# Car_Circuitry.net
KiCad netlist of a schematic drawn in Altium Designer
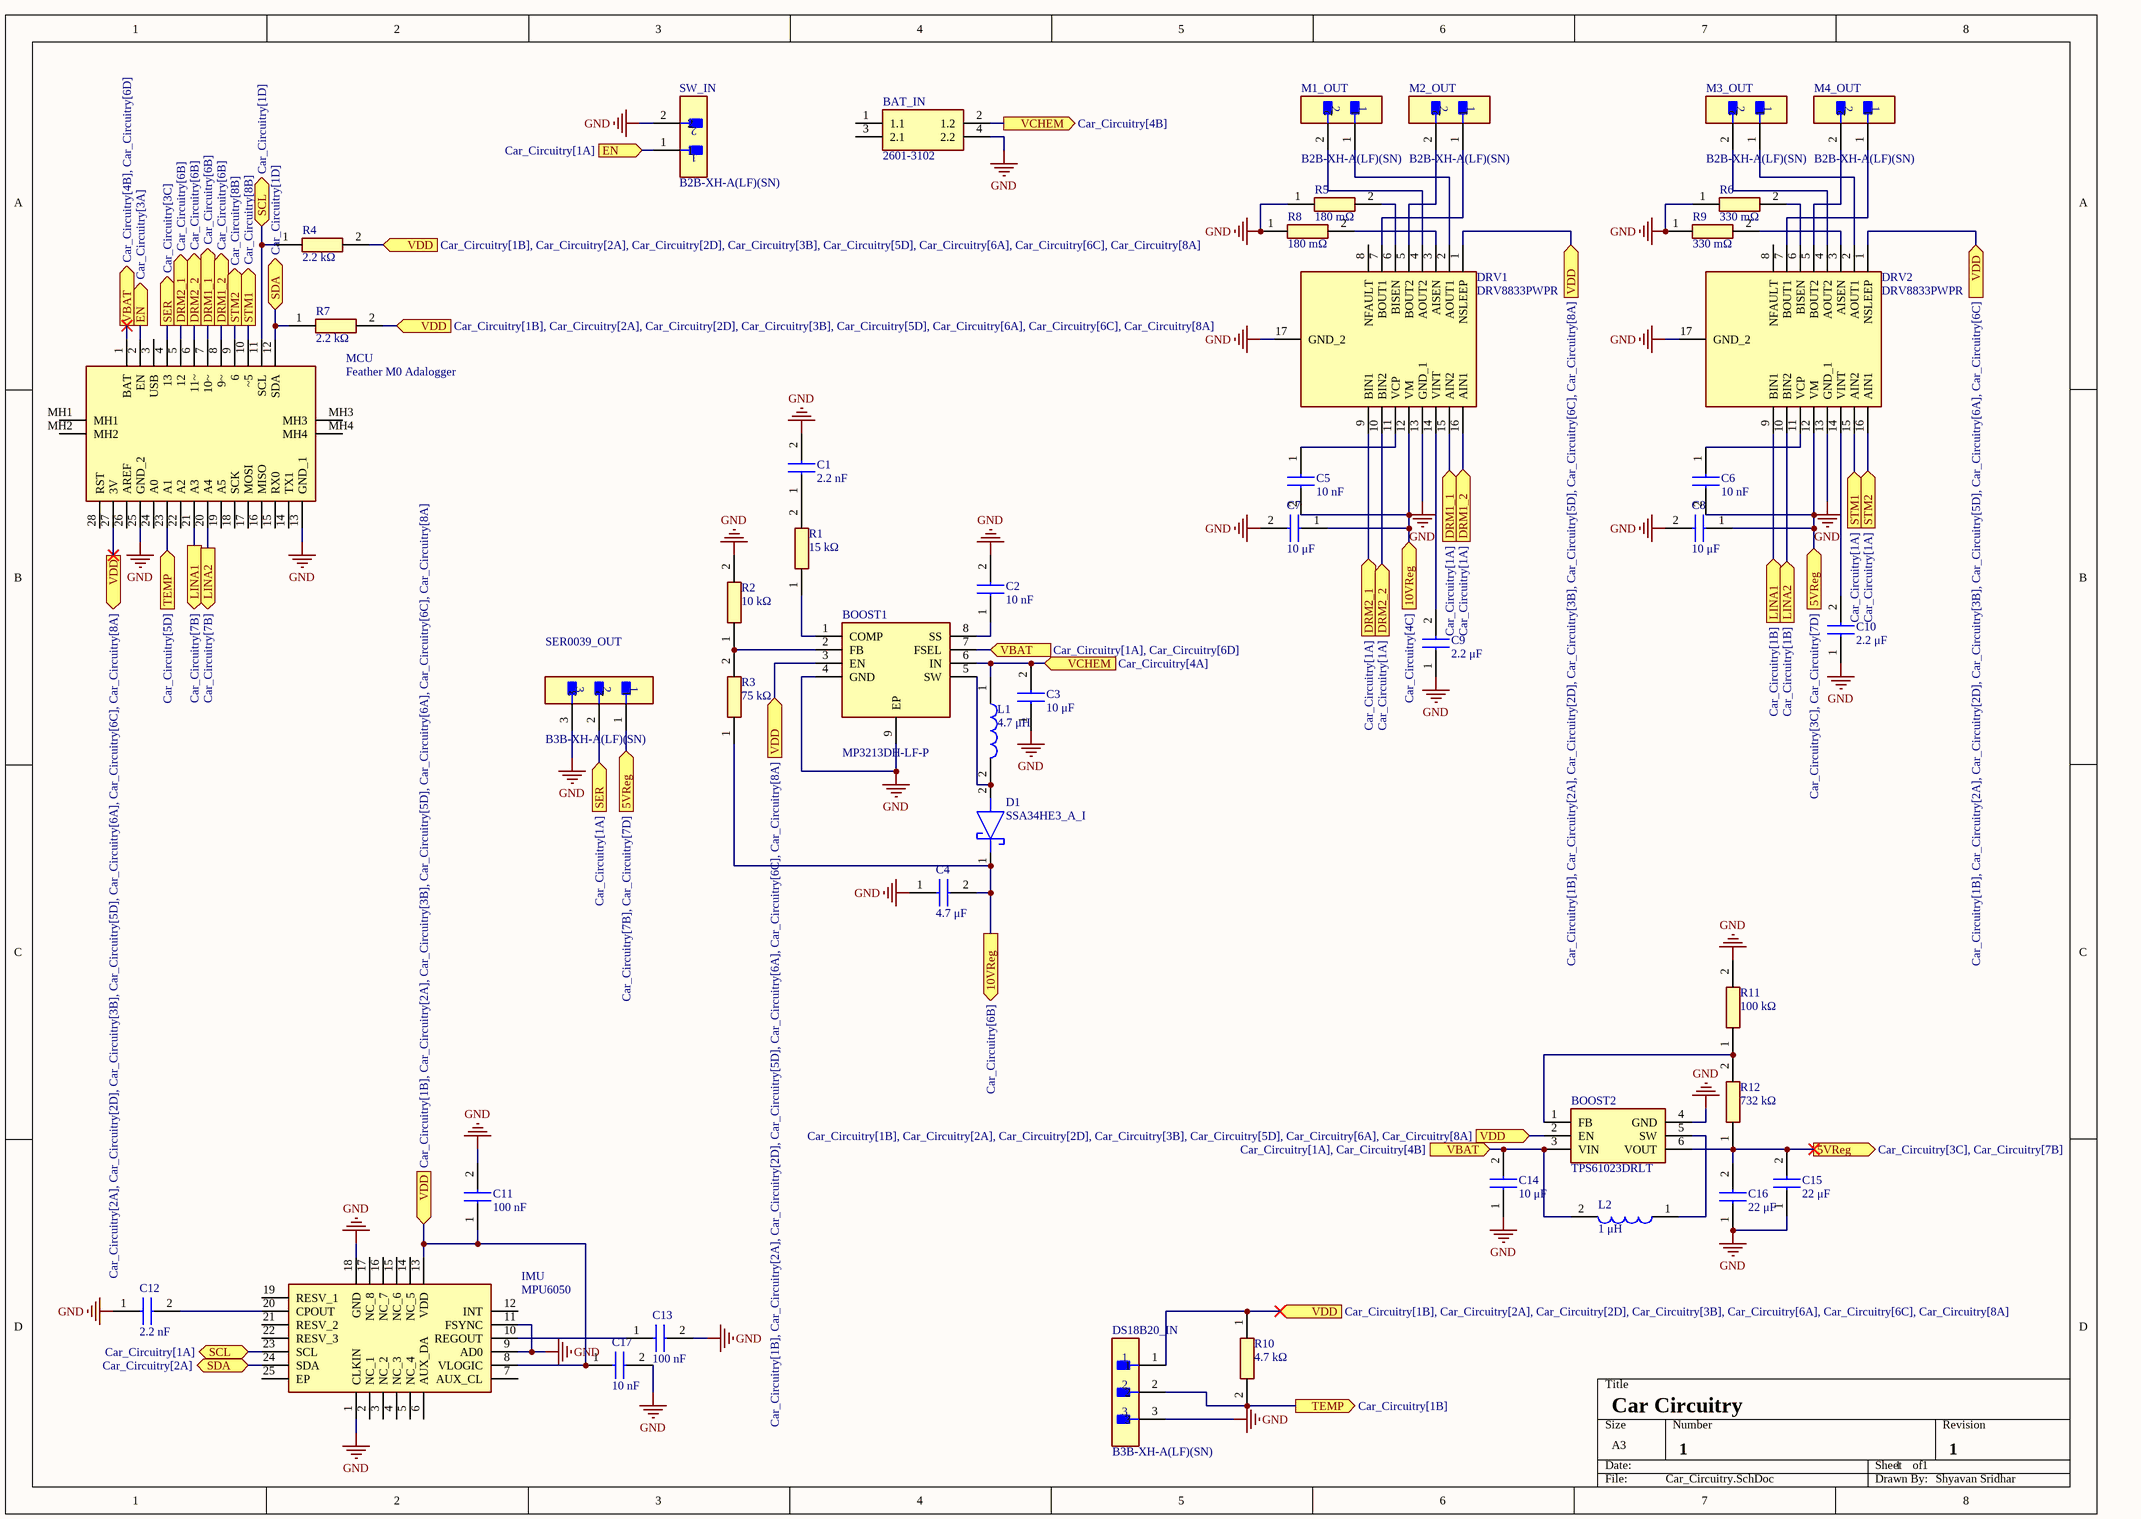
[diagram p0: Car_Circuitry.SchDoc]

(export (version "E")
  (design (tool "Eeschema 10.0.6"))
  (components
    (comp (ref "BAT_IN")
      (value "2601-3102")
      (footprint "SamacSys:26013102")
      (description "WAGO Terminal Block")
      (libsource (lib "*") (part "2601-3102"))
    )
    (comp (ref "BOOST1")
      (value "MP3213DH-LF-P")
      (footprint "SamacSys:SOP65P490X110-9N")
      (description "Integrated Circuit")
      (fields (field (name "MOUSER PART NUMBER") "946-MP3213DHLFP"))
      (libsource (lib "*") (part "MP3213DH-LF-P"))
    )
    (comp (ref "BOOST2")
      (value "TPS61023DRLT")
      (footprint "SamacSys:SOTFL50P160X60-6N")
      (description "Integrated Circuit")
      (fields (field (name "MOUSER PART NUMBER") "595-TPS61023DRLT"))
      (libsource (lib "*") (part "TPS61023DRLT"))
    )
    (comp (ref "C1")
      (value "2.2 nF")
      (footprint "SamacSys:CAPC2012X75N")
      (description "Capacitor")
      (fields (field (name "MANUFACTURER_PART_NUMBER") "CL21B222KBANNNC"))
      (libsource (lib "*") (part "CL21B222KBANNNC"))
    )
    (comp (ref "C2")
      (value "10 nF")
      (footprint "SamacSys:CAPC2012X75N")
      (description "Capacitor")
      (fields
        (field (name "MANUFACTURER_PART_NUMBER") "CL21B103KBANNNC")
        (field (name "MOUSER PART NUMBER") "187-CL21B103KBANNNC")
      )
      (libsource (lib "*") (part "CL21B103KBANNNC"))
    )
    (comp (ref "C3")
      (value "10 μF")
      (footprint "SamacSys:CAPC2012X140N")
      (description "Capacitor")
      (fields
        (field (name "MANUFACTURER_PART_NUMBER") "CL21B106KOQNNNE")
        (field (name "MOUSER PART NUMBER") "187-CL21B106KOQNNNE")
      )
      (libsource (lib "*") (part "CL21B106KOQNNNE"))
    )
    (comp (ref "C4")
      (value "4.7 μF")
      (footprint "SamacSys:CAPC2012X135N")
      (description "Capacitor")
      (fields
        (field (name "MANUFACTURER_PART_NUMBER") "CL21B475KOFNNNE")
        (field (name "MOUSER PART NUMBER") "187-CL21B475KOFNNNE")
      )
      (libsource (lib "*") (part "CL21B475KOFNNNE"))
    )
    (comp (ref "C5")
      (value "10 nF")
      (footprint "SamacSys:CAPC2012X75N")
      (description "Capacitor")
      (fields
        (field (name "MANUFACTURER_PART_NUMBER") "CL21B103KBANNNC")
        (field (name "MOUSER PART NUMBER") "187-CL21B103KBANNNC")
      )
      (libsource (lib "*") (part "CL21B103KBANNNC"))
    )
    (comp (ref "C6")
      (value "10 nF")
      (footprint "SamacSys:CAPC2012X75N")
      (description "Capacitor")
      (fields
        (field (name "MANUFACTURER_PART_NUMBER") "CL21B103KBANNNC")
        (field (name "MOUSER PART NUMBER") "187-CL21B103KBANNNC")
      )
      (libsource (lib "*") (part "CL21B103KBANNNC"))
    )
    (comp (ref "C7")
      (value "10 μF")
      (footprint "SamacSys:CAPC2012X140N")
      (description "Capacitor")
      (fields
        (field (name "MANUFACTURER_PART_NUMBER") "CL21B106KOQNNNE")
        (field (name "MOUSER PART NUMBER") "187-CL21B106KOQNNNE")
      )
      (libsource (lib "*") (part "CL21B106KOQNNNE"))
    )
    (comp (ref "C8")
      (value "10 μF")
      (footprint "SamacSys:CAPC2012X140N")
      (description "Capacitor")
      (fields
        (field (name "MANUFACTURER_PART_NUMBER") "CL21B106KOQNNNE")
        (field (name "MOUSER PART NUMBER") "187-CL21B106KOQNNNE")
      )
      (libsource (lib "*") (part "CL21B106KOQNNNE"))
    )
    (comp (ref "C9")
      (value "2.2 μF")
      (footprint "SamacSys:CAPC2012X135N")
      (description "Capacitor")
      (fields (field (name "MANUFACTURER_PART_NUMBER") "CL21B225KAFNNWE"))
      (libsource (lib "*") (part "CL21B225KAFNNWE"))
    )
    (comp (ref "C10")
      (value "2.2 μF")
      (footprint "SamacSys:CAPC2012X135N")
      (description "Capacitor")
      (fields (field (name "MANUFACTURER_PART_NUMBER") "CL21B225KAFNNWE"))
      (libsource (lib "*") (part "CL21B225KAFNNWE"))
    )
    (comp (ref "C11")
      (value "100 nF")
      (footprint "SamacSys:CAPC2012X95N")
      (description "Capacitor")
      (fields
        (field (name "MANUFACTURER_PART_NUMBER") "CL21B104KBCNNNC")
        (field (name "MOUSER PART NUMBER") "187-CL21B104KBCNNNC")
      )
      (libsource (lib "*") (part "CL21B104KBCNNNC"))
    )
    (comp (ref "C12")
      (value "2.2 nF")
      (footprint "SamacSys:CAPC2012X75N")
      (description "Capacitor")
      (fields (field (name "MANUFACTURER_PART_NUMBER") "CL21B222KBANNNC"))
      (libsource (lib "*") (part "CL21B222KBANNNC"))
    )
    (comp (ref "C13")
      (value "100 nF")
      (footprint "SamacSys:CAPC2012X95N")
      (description "Capacitor")
      (fields
        (field (name "MANUFACTURER_PART_NUMBER") "CL21B104KBCNNNC")
        (field (name "MOUSER PART NUMBER") "187-CL21B104KBCNNNC")
      )
      (libsource (lib "*") (part "CL21B104KBCNNNC"))
    )
    (comp (ref "C14")
      (value "10 μF")
      (footprint "SamacSys:CAPC2012X140N")
      (description "Capacitor")
      (fields
        (field (name "MANUFACTURER_PART_NUMBER") "CL21B106KOQNNNE")
        (field (name "MOUSER PART NUMBER") "187-CL21B106KOQNNNE")
      )
      (libsource (lib "*") (part "CL21B106KOQNNNE"))
    )
    (comp (ref "C15")
      (value "22 μF")
      (footprint "SamacSys:CAPC3216X180N")
      (description "Capacitor")
      (fields
        (field (name "MANUFACTURER_PART_NUMBER") "CL31B226KPHNNNE")
        (field (name "MOUSER PART NUMBER") "187-CL31B226KPHNNNE")
      )
      (libsource (lib "*") (part "CL31B226KPHNNNE"))
    )
    (comp (ref "C16")
      (value "22 μF")
      (footprint "SamacSys:CAPC3216X180N")
      (description "Capacitor")
      (fields
        (field (name "MANUFACTURER_PART_NUMBER") "CL31B226KPHNNNE")
        (field (name "MOUSER PART NUMBER") "187-CL31B226KPHNNNE")
      )
      (libsource (lib "*") (part "CL31B226KPHNNNE"))
    )
    (comp (ref "C17")
      (value "10 nF")
      (footprint "SamacSys:CAPC2012X75N")
      (description "Capacitor")
      (fields
        (field (name "MANUFACTURER_PART_NUMBER") "CL21B103KBANNNC")
        (field (name "MOUSER PART NUMBER") "187-CL21B103KBANNNC")
      )
      (libsource (lib "*") (part "CL21B103KBANNNC"))
    )
    (comp (ref "D1")
      (value "SSA34HE3_A_I")
      (footprint "SamacSys:DIONM5127X229N")
      (description "Schottky Diode")
      (fields
        (field (name "MANUFACTURER_PART_NUMBER") "SSA34HE3_A/I")
        (field (name "MOUSER PART NUMBER") "78-SSA34HE3_A/I")
      )
      (libsource (lib "*") (part "SSA34HE3_A_I"))
    )
    (comp (ref "DRV1")
      (value "DRV8833PWPR")
      (footprint "SamacSys:SOP65P640X120-17N")
      (description "Integrated Circuit")
      (fields
        (field (name "MANUFACTURER_PART_NUMBER") "DRV8833PWP")
        (field (name "MOUSER PART NUMBER") "595-DRV8833PWP")
      )
      (libsource (lib "*") (part "DRV8833PWP"))
    )
    (comp (ref "DRV2")
      (value "DRV8833PWPR")
      (footprint "SamacSys:SOP65P640X120-17N")
      (description "Integrated Circuit")
      (fields
        (field (name "MANUFACTURER_PART_NUMBER") "DRV8833PWP")
        (field (name "MOUSER PART NUMBER") "595-DRV8833PWP")
      )
      (libsource (lib "*") (part "DRV8833PWP"))
    )
    (comp (ref "DS18B20_IN")
      (value "B3B-XH-A(LF)(SN)")
      (footprint "FP-B3B-XH-A_LF_SN-MFG")
      (description "CONN HEADER VERT 3POS 2.5MM")
      (libsource (lib "") (part "0d3f023dd272f625e17a2be33dea85f_1"))
    )
    (comp (ref "IMU")
      (value "MPU6050")
      (footprint "SamacSys:MPU6050")
      (description "IMU")
      (libsource (lib "*") (part "MPU6050"))
    )
    (comp (ref "L1")
      (value "4.7 μH")
      (footprint "SamacSys:CDRH8D43NP4R7NC")
      (description "Inductor")
      (fields
        (field (name "MANUFACTURER_PART_NUMBER") "CDRH8D43NP-4R7NC")
        (field (name "MOUSER PART NUMBER") "851-CDRH8D43NP-4R7NC")
      )
      (libsource (lib "*") (part "CDRH8D43NP-4R7NC"))
    )
    (comp (ref "L2")
      (value "1 μH")
      (footprint "SamacSys:74438357010")
      (description "Inductor")
      (fields
        (field (name "MANUFACTURER_PART_NUMBER") "74438357010")
        (field (name "MOUSER PART NUMBER") "710-74438357010")
      )
      (libsource (lib "*") (part "74438357010"))
    )
    (comp (ref "M1_OUT")
      (value "B2B-XH-A(LF)(SN)")
      (footprint "FP-B2B-XH-A_LF_SN-MFG")
      (description "CONN HEADER VERT 2POS 2.5MM")
      (libsource (lib "Altium Content Vault") (part "3bc925449376181038e59eaffc5286c"))
    )
    (comp (ref "M2_OUT")
      (value "B2B-XH-A(LF)(SN)")
      (footprint "FP-B2B-XH-A_LF_SN-MFG")
      (description "CONN HEADER VERT 2POS 2.5MM")
      (libsource (lib "Altium Content Vault") (part "3bc925449376181038e59eaffc5286c"))
    )
    (comp (ref "M3_OUT")
      (value "B2B-XH-A(LF)(SN)")
      (footprint "FP-B2B-XH-A_LF_SN-MFG")
      (description "CONN HEADER VERT 2POS 2.5MM")
      (libsource (lib "Altium Content Vault") (part "3bc925449376181038e59eaffc5286c"))
    )
    (comp (ref "M4_OUT")
      (value "B2B-XH-A(LF)(SN)")
      (footprint "FP-B2B-XH-A_LF_SN-MFG")
      (description "CONN HEADER VERT 2POS 2.5MM")
      (libsource (lib "Altium Content Vault") (part "3bc925449376181038e59eaffc5286c"))
    )
    (comp (ref "MCU")
      (value "Feather M0 Adalogger")
      (footprint "SamacSys:2796")
      (description "Adafruit Microcontroller")
      (fields (field (name "MANUFACTURER_PART_NUMBER") "2796") (field (name "MOUSER PART NUMBER") "485-2796"))
      (libsource (lib "*") (part "2796"))
    )
    (comp (ref "R1")
      (value "15 kΩ")
      (footprint "SamacSys:RESC3216X70N")
      (description "Resistor")
      (fields (field (name "MANUFACTURER_PART_NUMBER") "RMCF1206FT15K0"))
      (libsource (lib "*") (part "RMCF1206FT15K0"))
    )
    (comp (ref "R2")
      (value "10 kΩ")
      (footprint "SamacSys:RESC3216X70N")
      (description "Resistor")
      (fields
        (field (name "MANUFACTURER_PART_NUMBER") "RMCF1206FT10K0")
        (field (name "MOUSER PART NUMBER") "708-RMCF1206FT10K0")
      )
      (libsource (lib "*") (part "RMCF1206FT10K0"))
    )
    (comp (ref "R3")
      (value "75 kΩ")
      (footprint "SamacSys:RESC3116X65N")
      (description "Resistor")
      (fields
        (field (name "MANUFACTURER_PART_NUMBER") "RC1206FR-0775KL")
        (field (name "MOUSER PART NUMBER") "603-RC1206FR-0775KL")
      )
      (libsource (lib "*") (part "RC1206FR-0775KL"))
    )
    (comp (ref "R4")
      (value "2.2 kΩ")
      (footprint "SamacSys:RESAD1042W49L330D178")
      (description "Resistor")
      (fields (field (name "MANUFACTURER_PART_NUMBER") "RNMF14FTC2K20"))
      (libsource (lib "*") (part "RNMF14FTC2K20"))
    )
    (comp (ref "R5")
      (value "180 mΩ")
      (footprint "SamacSys:ERJ6_B_BW_R_LW_CW_D")
      (description "Resistor")
      (fields
        (field (name "MANUFACTURER_PART_NUMBER") "ERJ-6DSFR18V")
        (field (name "MOUSER PART NUMBER") "667-ERJ-6DSFR18V")
      )
      (libsource (lib "*") (part "ERJ-6DSFR18V"))
    )
    (comp (ref "R6")
      (value "330 mΩ")
      (footprint "SamacSys:ERJ6_B_BW_R_LW_CW_D")
      (description "Resistor")
      (fields
        (field (name "MANUFACTURER_PART_NUMBER") "ERJ-6DQFR33V")
        (field (name "MOUSER PART NUMBER") "667-ERJ-6DQFR33V")
      )
      (libsource (lib "*") (part "ERJ-6DQFR33V"))
    )
    (comp (ref "R7")
      (value "2.2 kΩ")
      (footprint "SamacSys:RESAD1042W49L330D178")
      (description "Resistor")
      (fields (field (name "MANUFACTURER_PART_NUMBER") "RNMF14FTC2K20"))
      (libsource (lib "*") (part "RNMF14FTC2K20"))
    )
    (comp (ref "R8")
      (value "180 mΩ")
      (footprint "SamacSys:ERJ6_B_BW_R_LW_CW_D")
      (description "Resistor")
      (fields
        (field (name "MANUFACTURER_PART_NUMBER") "ERJ-6DSFR18V")
        (field (name "MOUSER PART NUMBER") "667-ERJ-6DSFR18V")
      )
      (libsource (lib "*") (part "ERJ-6DSFR18V"))
    )
    (comp (ref "R9")
      (value "330 mΩ")
      (footprint "SamacSys:ERJ6_B_BW_R_LW_CW_D")
      (description "Resistor")
      (fields
        (field (name "MANUFACTURER_PART_NUMBER") "ERJ-6DQFR33V")
        (field (name "MOUSER PART NUMBER") "667-ERJ-6DQFR33V")
      )
      (libsource (lib "*") (part "ERJ-6DQFR33V"))
    )
    (comp (ref "R10")
      (value "4.7 kΩ")
      (footprint "SamacSys:RESAD1530W60L610D230")
      (description "Resistor")
      (fields
        (field (name "MANUFACTURER_PART_NUMBER") "CF1/4C472J")
        (field (name "MOUSER PART NUMBER") "660-CF1/4C472J")
      )
      (libsource (lib "*") (part "CF1_4C472J"))
    )
    (comp (ref "R11")
      (value "100 kΩ")
      (footprint "SamacSys:ERJ8ENF1000V")
      (description "Resistor")
      (fields
        (field (name "MANUFACTURER_PART_NUMBER") "ERJ-8ENF1003V")
        (field (name "MOUSER PART NUMBER") "667-ERJ-8ENF1003V")
      )
      (libsource (lib "*") (part "ERJ-8ENF1003V"))
    )
    (comp (ref "R12")
      (value "732 kΩ")
      (footprint "SamacSys:ERJ8ENF1000V")
      (description "Resistor")
      (fields
        (field (name "MANUFACTURER_PART_NUMBER") "ERJ-8ENF7323V")
        (field (name "MOUSER PART NUMBER") "667-ERJ-8ENF7323V")
      )
      (libsource (lib "*") (part "ERJ-8ENF7323V"))
    )
    (comp (ref "SER0039_OUT")
      (value "B3B-XH-A(LF)(SN)")
      (footprint "FP-B3B-XH-A_LF_SN-MFG")
      (description "CONN HEADER VERT 3POS 2.5MM")
      (libsource (lib "Altium Content Vault") (part "0d3f023dd272f625e17a2be33dea85f"))
    )
    (comp (ref "SW_IN")
      (value "B2B-XH-A(LF)(SN)")
      (footprint "FP-B2B-XH-A_LF_SN-MFG")
      (description "CONN HEADER VERT 2POS 2.5MM")
      (libsource (lib "") (part "3bc925449376181038e59eaffc5286c_1"))
    )
  )
  (nets
    (net (code "1") (name "/5VReg") (class "Default")
      (node (ref "BOOST2") (pin "6") (pinfunction "VOUT_6") (pintype "passive"))
      (node (ref "C15") (pin "2") (pinfunction "2_2") (pintype "passive"))
      (node (ref "C16") (pin "2") (pinfunction "2_2") (pintype "passive"))
      (node (ref "C6") (pin "2") (pinfunction "2_2") (pintype "passive"))
      (node (ref "C8") (pin "1") (pinfunction "1_1") (pintype "passive"))
      (node (ref "DRV2") (pin "12") (pinfunction "VM_12") (pintype "passive"))
      (node (ref "R12") (pin "1") (pinfunction "1_1") (pintype "passive"))
      (node (ref "SER0039_OUT") (pin "1") (pinfunction "1_1") (pintype "passive"))
    )
    (net (code "2") (name "/10VReg") (class "Default")
      (node (ref "C4") (pin "2") (pinfunction "2_2") (pintype "passive"))
      (node (ref "C5") (pin "2") (pinfunction "2_2") (pintype "passive"))
      (node (ref "C7") (pin "1") (pinfunction "1_1") (pintype "passive"))
      (node (ref "D1") (pin "1") (pinfunction "K_1") (pintype "passive"))
      (node (ref "DRV1") (pin "12") (pinfunction "VM_12") (pintype "passive"))
      (node (ref "R3") (pin "1") (pinfunction "1_1") (pintype "passive"))
    )
    (net (code "3") (name "/DRM1_1") (class "Default")
      (node (ref "DRV1") (pin "15") (pinfunction "AIN2_15") (pintype "passive"))
      (node (ref "MCU") (pin "7") (pinfunction "10~_7") (pintype "passive"))
    )
    (net (code "4") (name "/DRM1_2") (class "Default")
      (node (ref "DRV1") (pin "16") (pinfunction "AIN1_16") (pintype "passive"))
      (node (ref "MCU") (pin "8") (pinfunction "9~_8") (pintype "passive"))
    )
    (net (code "5") (name "/DRM2_1") (class "Default")
      (node (ref "DRV1") (pin "9") (pinfunction "BIN1_9") (pintype "passive"))
      (node (ref "MCU") (pin "5") (pinfunction "12_5") (pintype "passive"))
    )
    (net (code "6") (name "/DRM2_2") (class "Default")
      (node (ref "DRV1") (pin "10") (pinfunction "BIN2_10") (pintype "passive"))
      (node (ref "MCU") (pin "6") (pinfunction "11~_6") (pintype "passive"))
    )
    (net (code "7") (name "/EN") (class "Default")
      (node (ref "MCU") (pin "2") (pinfunction "EN_2") (pintype "passive"))
      (node (ref "SW_IN") (pin "1") (pinfunction "1_1") (pintype "passive"))
    )
    (net (code "8") (name "/LINA1") (class "Default")
      (node (ref "DRV2") (pin "9") (pinfunction "BIN1_9") (pintype "passive"))
      (node (ref "MCU") (pin "21") (pinfunction "A3_21") (pintype "passive"))
    )
    (net (code "9") (name "/LINA2") (class "Default")
      (node (ref "DRV2") (pin "10") (pinfunction "BIN2_10") (pintype "passive"))
      (node (ref "MCU") (pin "20") (pinfunction "A4_20") (pintype "passive"))
    )
    (net (code "10") (name "/SCL") (class "Default")
      (node (ref "IMU") (pin "23") (pinfunction "SCL_23") (pintype "passive"))
      (node (ref "MCU") (pin "11") (pinfunction "SCL_11") (pintype "passive"))
      (node (ref "R4") (pin "1") (pinfunction "1_1") (pintype "passive"))
    )
    (net (code "11") (name "/SDA") (class "Default")
      (node (ref "IMU") (pin "24") (pinfunction "SDA_24") (pintype "passive"))
      (node (ref "MCU") (pin "12") (pinfunction "SDA_12") (pintype "passive"))
      (node (ref "R7") (pin "1") (pinfunction "1_1") (pintype "passive"))
    )
    (net (code "12") (name "/SER") (class "Default")
      (node (ref "MCU") (pin "4") (pinfunction "13_4") (pintype "passive"))
      (node (ref "SER0039_OUT") (pin "2") (pinfunction "2_2") (pintype "passive"))
    )
    (net (code "13") (name "/STM1") (class "Default")
      (node (ref "DRV2") (pin "15") (pinfunction "AIN2_15") (pintype "passive"))
      (node (ref "MCU") (pin "10") (pinfunction "~5_10") (pintype "passive"))
    )
    (net (code "14") (name "/STM2") (class "Default")
      (node (ref "DRV2") (pin "16") (pinfunction "AIN1_16") (pintype "passive"))
      (node (ref "MCU") (pin "9") (pinfunction "6_9") (pintype "passive"))
    )
    (net (code "15") (name "/TEMP") (class "Default")
      (node (ref "DS18B20_IN") (pin "2") (pinfunction "2_2") (pintype "passive"))
      (node (ref "MCU") (pin "23") (pinfunction "A1_23") (pintype "passive"))
      (node (ref "R10") (pin "2") (pinfunction "2_2") (pintype "passive"))
    )
    (net (code "16") (name "/VBAT") (class "Default")
      (node (ref "BOOST1") (pin "7") (pinfunction "FSEL_7") (pintype "passive"))
      (node (ref "BOOST2") (pin "3") (pinfunction "VIN_3") (pintype "passive"))
      (node (ref "C14") (pin "2") (pinfunction "2_2") (pintype "passive"))
      (node (ref "L2") (pin "2") (pinfunction "2_2") (pintype "passive"))
      (node (ref "MCU") (pin "1") (pinfunction "BAT_1") (pintype "passive"))
    )
    (net (code "17") (name "/VCHEM") (class "Default")
      (node (ref "BAT_IN") (pin "2") (pinfunction "1.2_2") (pintype "passive"))
      (node (ref "BOOST1") (pin "6") (pinfunction "IN_6") (pintype "passive"))
      (node (ref "C3") (pin "2") (pinfunction "2_2") (pintype "passive"))
      (node (ref "L1") (pin "1") (pinfunction "1_1") (pintype "passive"))
    )
    (net (code "18") (name "/VDD") (class "Default")
      (node (ref "BOOST1") (pin "3") (pinfunction "EN_3") (pintype "passive"))
      (node (ref "BOOST2") (pin "2") (pinfunction "EN_2") (pintype "passive"))
      (node (ref "C11") (pin "1") (pinfunction "1_1") (pintype "passive"))
      (node (ref "C17") (pin "1") (pinfunction "1_1") (pintype "passive"))
      (node (ref "DRV1") (pin "1") (pinfunction "NSLEEP_1") (pintype "passive"))
      (node (ref "DRV2") (pin "1") (pinfunction "NSLEEP_1") (pintype "passive"))
      (node (ref "DS18B20_IN") (pin "1") (pinfunction "1_1") (pintype "passive"))
      (node (ref "IMU") (pin "13") (pinfunction "VDD_13") (pintype "passive"))
      (node (ref "IMU") (pin "8") (pinfunction "VLOGIC_8") (pintype "passive"))
      (node (ref "MCU") (pin "27") (pinfunction "3V_27") (pintype "passive"))
      (node (ref "R10") (pin "1") (pinfunction "1_1") (pintype "passive"))
      (node (ref "R4") (pin "2") (pinfunction "2_2") (pintype "passive"))
      (node (ref "R7") (pin "2") (pinfunction "2_2") (pintype "passive"))
    )
    (net (code "19") (name "GND") (class "Default")
      (node (ref "BAT_IN") (pin "4") (pinfunction "2.2_4") (pintype "passive"))
      (node (ref "BOOST1") (pin "4") (pinfunction "GND_4") (pintype "passive"))
      (node (ref "BOOST1") (pin "9") (pinfunction "EP_9") (pintype "passive"))
      (node (ref "BOOST2") (pin "4") (pinfunction "GND_4") (pintype "passive"))
      (node (ref "C1") (pin "2") (pinfunction "2_2") (pintype "passive"))
      (node (ref "C10") (pin "1") (pinfunction "1_1") (pintype "passive"))
      (node (ref "C11") (pin "2") (pinfunction "2_2") (pintype "passive"))
      (node (ref "C12") (pin "1") (pinfunction "1_1") (pintype "passive"))
      (node (ref "C13") (pin "2") (pinfunction "2_2") (pintype "passive"))
      (node (ref "C14") (pin "1") (pinfunction "1_1") (pintype "passive"))
      (node (ref "C15") (pin "1") (pinfunction "1_1") (pintype "passive"))
      (node (ref "C16") (pin "1") (pinfunction "1_1") (pintype "passive"))
      (node (ref "C17") (pin "2") (pinfunction "2_2") (pintype "passive"))
      (node (ref "C2") (pin "2") (pinfunction "2_2") (pintype "passive"))
      (node (ref "C3") (pin "1") (pinfunction "1_1") (pintype "passive"))
      (node (ref "C4") (pin "1") (pinfunction "1_1") (pintype "passive"))
      (node (ref "C7") (pin "2") (pinfunction "2_2") (pintype "passive"))
      (node (ref "C8") (pin "2") (pinfunction "2_2") (pintype "passive"))
      (node (ref "C9") (pin "1") (pinfunction "1_1") (pintype "passive"))
      (node (ref "DRV1") (pin "13") (pinfunction "GND_1_13") (pintype "passive"))
      (node (ref "DRV1") (pin "17") (pinfunction "GND_2_17") (pintype "passive"))
      (node (ref "DRV2") (pin "13") (pinfunction "GND_1_13") (pintype "passive"))
      (node (ref "DRV2") (pin "17") (pinfunction "GND_2_17") (pintype "passive"))
      (node (ref "DS18B20_IN") (pin "3") (pinfunction "3_3") (pintype "passive"))
      (node (ref "IMU") (pin "1") (pinfunction "CLKIN_1") (pintype "passive"))
      (node (ref "IMU") (pin "11") (pinfunction "FSYNC_11") (pintype "passive"))
      (node (ref "IMU") (pin "18") (pinfunction "GND_18") (pintype "passive"))
      (node (ref "IMU") (pin "9") (pinfunction "AD0_9") (pintype "passive"))
      (node (ref "MCU") (pin "13") (pinfunction "GND_1_13") (pintype "passive"))
      (node (ref "MCU") (pin "25") (pinfunction "GND_2_25") (pintype "passive"))
      (node (ref "R11") (pin "2") (pinfunction "2_2") (pintype "passive"))
      (node (ref "R2") (pin "2") (pinfunction "2_2") (pintype "passive"))
      (node (ref "R5") (pin "1") (pinfunction "1_1") (pintype "passive"))
      (node (ref "R6") (pin "1") (pinfunction "1_1") (pintype "passive"))
      (node (ref "R8") (pin "1") (pinfunction "1_1") (pintype "passive"))
      (node (ref "R9") (pin "1") (pinfunction "1_1") (pintype "passive"))
      (node (ref "SER0039_OUT") (pin "3") (pinfunction "3_3") (pintype "passive"))
      (node (ref "SW_IN") (pin "2") (pinfunction "2_2") (pintype "passive"))
    )
    (net (code "20") (name "Net-(BOOST1-COMP)") (class "Default")
      (node (ref "BOOST1") (pin "1") (pinfunction "COMP_1") (pintype "passive"))
      (node (ref "R1") (pin "1") (pinfunction "1_1") (pintype "passive"))
    )
    (net (code "21") (name "Net-(BOOST1-FB)") (class "Default")
      (node (ref "BOOST1") (pin "2") (pinfunction "FB_2") (pintype "passive"))
      (node (ref "R2") (pin "1") (pinfunction "1_1") (pintype "passive"))
      (node (ref "R3") (pin "2") (pinfunction "2_2") (pintype "passive"))
    )
    (net (code "22") (name "Net-(BOOST1-SS)") (class "Default")
      (node (ref "BOOST1") (pin "8") (pinfunction "SS_8") (pintype "passive"))
      (node (ref "C2") (pin "1") (pinfunction "1_1") (pintype "passive"))
    )
    (net (code "23") (name "Net-(BOOST1-SW)") (class "Default")
      (node (ref "BOOST1") (pin "5") (pinfunction "SW_5") (pintype "passive"))
      (node (ref "D1") (pin "2") (pinfunction "A_2") (pintype "passive"))
      (node (ref "L1") (pin "2") (pinfunction "2_2") (pintype "passive"))
    )
    (net (code "24") (name "Net-(BOOST2-FB)") (class "Default")
      (node (ref "BOOST2") (pin "1") (pinfunction "FB_1") (pintype "passive"))
      (node (ref "R11") (pin "1") (pinfunction "1_1") (pintype "passive"))
      (node (ref "R12") (pin "2") (pinfunction "2_2") (pintype "passive"))
    )
    (net (code "25") (name "Net-(BOOST2-SW)") (class "Default")
      (node (ref "BOOST2") (pin "5") (pinfunction "SW_5") (pintype "passive"))
      (node (ref "L2") (pin "1") (pinfunction "1_1") (pintype "passive"))
    )
    (net (code "26") (name "Net-(C1-Pad1)") (class "Default")
      (node (ref "C1") (pin "1") (pinfunction "1_1") (pintype "passive"))
      (node (ref "R1") (pin "2") (pinfunction "2_2") (pintype "passive"))
    )
    (net (code "27") (name "Net-(DRV1-AISEN)") (class "Default")
      (node (ref "DRV1") (pin "3") (pinfunction "AISEN_3") (pintype "passive"))
      (node (ref "R8") (pin "2") (pinfunction "2_2") (pintype "passive"))
    )
    (net (code "28") (name "Net-(DRV1-AOUT1)") (class "Default")
      (node (ref "DRV1") (pin "2") (pinfunction "AOUT1_2") (pintype "passive"))
      (node (ref "M1_OUT") (pin "1") (pinfunction "1_1") (pintype "passive"))
    )
    (net (code "29") (name "Net-(DRV1-AOUT2)") (class "Default")
      (node (ref "DRV1") (pin "4") (pinfunction "AOUT2_4") (pintype "passive"))
      (node (ref "M1_OUT") (pin "2") (pinfunction "2_2") (pintype "passive"))
    )
    (net (code "30") (name "Net-(DRV1-BISEN)") (class "Default")
      (node (ref "DRV1") (pin "6") (pinfunction "BISEN_6") (pintype "passive"))
      (node (ref "R5") (pin "2") (pinfunction "2_2") (pintype "passive"))
    )
    (net (code "31") (name "Net-(DRV1-BOUT1)") (class "Default")
      (node (ref "DRV1") (pin "7") (pinfunction "BOUT1_7") (pintype "passive"))
      (node (ref "M2_OUT") (pin "1") (pinfunction "1_1") (pintype "passive"))
    )
    (net (code "32") (name "Net-(DRV1-BOUT2)") (class "Default")
      (node (ref "DRV1") (pin "5") (pinfunction "BOUT2_5") (pintype "passive"))
      (node (ref "M2_OUT") (pin "2") (pinfunction "2_2") (pintype "passive"))
    )
    (net (code "33") (name "Net-(DRV1-VCP)") (class "Default")
      (node (ref "C5") (pin "1") (pinfunction "1_1") (pintype "passive"))
      (node (ref "DRV1") (pin "11") (pinfunction "VCP_11") (pintype "passive"))
    )
    (net (code "34") (name "Net-(DRV1-VINT)") (class "Default")
      (node (ref "C9") (pin "2") (pinfunction "2_2") (pintype "passive"))
      (node (ref "DRV1") (pin "14") (pinfunction "VINT_14") (pintype "passive"))
    )
    (net (code "35") (name "Net-(DRV2-AISEN)") (class "Default")
      (node (ref "DRV2") (pin "3") (pinfunction "AISEN_3") (pintype "passive"))
      (node (ref "R9") (pin "2") (pinfunction "2_2") (pintype "passive"))
    )
    (net (code "36") (name "Net-(DRV2-AOUT1)") (class "Default")
      (node (ref "DRV2") (pin "2") (pinfunction "AOUT1_2") (pintype "passive"))
      (node (ref "M3_OUT") (pin "1") (pinfunction "1_1") (pintype "passive"))
    )
    (net (code "37") (name "Net-(DRV2-AOUT2)") (class "Default")
      (node (ref "DRV2") (pin "4") (pinfunction "AOUT2_4") (pintype "passive"))
      (node (ref "M3_OUT") (pin "2") (pinfunction "2_2") (pintype "passive"))
    )
    (net (code "38") (name "Net-(DRV2-BISEN)") (class "Default")
      (node (ref "DRV2") (pin "6") (pinfunction "BISEN_6") (pintype "passive"))
      (node (ref "R6") (pin "2") (pinfunction "2_2") (pintype "passive"))
    )
    (net (code "39") (name "Net-(DRV2-BOUT1)") (class "Default")
      (node (ref "DRV2") (pin "7") (pinfunction "BOUT1_7") (pintype "passive"))
      (node (ref "M4_OUT") (pin "1") (pinfunction "1_1") (pintype "passive"))
    )
    (net (code "40") (name "Net-(DRV2-BOUT2)") (class "Default")
      (node (ref "DRV2") (pin "5") (pinfunction "BOUT2_5") (pintype "passive"))
      (node (ref "M4_OUT") (pin "2") (pinfunction "2_2") (pintype "passive"))
    )
    (net (code "41") (name "Net-(DRV2-VCP)") (class "Default")
      (node (ref "C6") (pin "1") (pinfunction "1_1") (pintype "passive"))
      (node (ref "DRV2") (pin "11") (pinfunction "VCP_11") (pintype "passive"))
    )
    (net (code "42") (name "Net-(DRV2-VINT)") (class "Default")
      (node (ref "C10") (pin "2") (pinfunction "2_2") (pintype "passive"))
      (node (ref "DRV2") (pin "14") (pinfunction "VINT_14") (pintype "passive"))
    )
    (net (code "43") (name "Net-(IMU-CPOUT)") (class "Default")
      (node (ref "C12") (pin "2") (pinfunction "2_2") (pintype "passive"))
      (node (ref "IMU") (pin "20") (pinfunction "CPOUT_20") (pintype "passive"))
    )
    (net (code "44") (name "Net-(IMU-REGOUT)") (class "Default")
      (node (ref "C13") (pin "1") (pinfunction "1_1") (pintype "passive"))
      (node (ref "IMU") (pin "10") (pinfunction "REGOUT_10") (pintype "passive"))
    )
    (net (code "45") (name "unconnected-(BAT_IN-1.1-Pad1)") (class "Default")
      (node (ref "BAT_IN") (pin "1") (pinfunction "1.1_1") (pintype "passive"))
    )
    (net (code "46") (name "unconnected-(BAT_IN-2.1-Pad3)") (class "Default")
      (node (ref "BAT_IN") (pin "3") (pinfunction "2.1_3") (pintype "passive"))
    )
    (net (code "47") (name "unconnected-(DRV1-NFAULT-Pad8)") (class "Default")
      (node (ref "DRV1") (pin "8") (pinfunction "NFAULT_8") (pintype "passive"))
    )
    (net (code "48") (name "unconnected-(DRV2-NFAULT-Pad8)") (class "Default")
      (node (ref "DRV2") (pin "8") (pinfunction "NFAULT_8") (pintype "passive"))
    )
    (net (code "49") (name "unconnected-(IMU-AUX_CL-Pad7)") (class "Default")
      (node (ref "IMU") (pin "7") (pinfunction "AUX_CL_7") (pintype "passive"))
    )
    (net (code "50") (name "unconnected-(IMU-AUX_DA-Pad6)") (class "Default")
      (node (ref "IMU") (pin "6") (pinfunction "AUX_DA_6") (pintype "passive"))
    )
    (net (code "51") (name "unconnected-(IMU-EP-Pad25)") (class "Default")
      (node (ref "IMU") (pin "25") (pinfunction "EP_25") (pintype "passive"))
    )
    (net (code "52") (name "unconnected-(IMU-INT-Pad12)") (class "Default")
      (node (ref "IMU") (pin "12") (pinfunction "INT_12") (pintype "passive"))
    )
    (net (code "53") (name "unconnected-(IMU-NC_1-Pad2)") (class "Default")
      (node (ref "IMU") (pin "2") (pinfunction "NC_1_2") (pintype "passive"))
    )
    (net (code "54") (name "unconnected-(IMU-NC_2-Pad3)") (class "Default")
      (node (ref "IMU") (pin "3") (pinfunction "NC_2_3") (pintype "passive"))
    )
    (net (code "55") (name "unconnected-(IMU-NC_3-Pad4)") (class "Default")
      (node (ref "IMU") (pin "4") (pinfunction "NC_3_4") (pintype "passive"))
    )
    (net (code "56") (name "unconnected-(IMU-NC_4-Pad5)") (class "Default")
      (node (ref "IMU") (pin "5") (pinfunction "NC_4_5") (pintype "passive"))
    )
    (net (code "57") (name "unconnected-(IMU-NC_5-Pad14)") (class "Default")
      (node (ref "IMU") (pin "14") (pinfunction "NC_5_14") (pintype "passive"))
    )
    (net (code "58") (name "unconnected-(IMU-NC_6-Pad15)") (class "Default")
      (node (ref "IMU") (pin "15") (pinfunction "NC_6_15") (pintype "passive"))
    )
    (net (code "59") (name "unconnected-(IMU-NC_7-Pad16)") (class "Default")
      (node (ref "IMU") (pin "16") (pinfunction "NC_7_16") (pintype "passive"))
    )
    (net (code "60") (name "unconnected-(IMU-NC_8-Pad17)") (class "Default")
      (node (ref "IMU") (pin "17") (pinfunction "NC_8_17") (pintype "passive"))
    )
    (net (code "61") (name "unconnected-(IMU-RESV_1-Pad19)") (class "Default")
      (node (ref "IMU") (pin "19") (pinfunction "RESV_1_19") (pintype "passive"))
    )
    (net (code "62") (name "unconnected-(IMU-RESV_2-Pad21)") (class "Default")
      (node (ref "IMU") (pin "21") (pinfunction "RESV_2_21") (pintype "passive"))
    )
    (net (code "63") (name "unconnected-(IMU-RESV_3-Pad22)") (class "Default")
      (node (ref "IMU") (pin "22") (pinfunction "RESV_3_22") (pintype "passive"))
    )
    (net (code "64") (name "unconnected-(MCU-A0-Pad24)") (class "Default")
      (node (ref "MCU") (pin "24") (pinfunction "A0_24") (pintype "passive"))
    )
    (net (code "65") (name "unconnected-(MCU-A2-Pad22)") (class "Default")
      (node (ref "MCU") (pin "22") (pinfunction "A2_22") (pintype "passive"))
    )
    (net (code "66") (name "unconnected-(MCU-A5-Pad19)") (class "Default")
      (node (ref "MCU") (pin "19") (pinfunction "A5_19") (pintype "passive"))
    )
    (net (code "67") (name "unconnected-(MCU-AREF-Pad26)") (class "Default")
      (node (ref "MCU") (pin "26") (pinfunction "AREF_26") (pintype "passive"))
    )
    (net (code "68") (name "unconnected-(MCU-MISO-Pad16)") (class "Default")
      (node (ref "MCU") (pin "16") (pinfunction "MISO_16") (pintype "passive"))
    )
    (net (code "69") (name "unconnected-(MCU-MOSI-Pad17)") (class "Default")
      (node (ref "MCU") (pin "17") (pinfunction "MOSI_17") (pintype "passive"))
    )
    (net (code "70") (name "unconnected-(MCU-PadMH1)") (class "Default")
      (node (ref "MCU") (pin "MH1") (pinfunction "MH1_MH1") (pintype "passive"))
    )
    (net (code "71") (name "unconnected-(MCU-PadMH2)") (class "Default")
      (node (ref "MCU") (pin "MH2") (pinfunction "MH2_MH2") (pintype "passive"))
    )
    (net (code "72") (name "unconnected-(MCU-PadMH3)") (class "Default")
      (node (ref "MCU") (pin "MH3") (pinfunction "MH3_MH3") (pintype "passive"))
    )
    (net (code "73") (name "unconnected-(MCU-PadMH4)") (class "Default")
      (node (ref "MCU") (pin "MH4") (pinfunction "MH4_MH4") (pintype "passive"))
    )
    (net (code "74") (name "unconnected-(MCU-RST-Pad28)") (class "Default")
      (node (ref "MCU") (pin "28") (pinfunction "RST_28") (pintype "passive"))
    )
    (net (code "75") (name "unconnected-(MCU-RX0-Pad15)") (class "Default")
      (node (ref "MCU") (pin "15") (pinfunction "RX0_15") (pintype "passive"))
    )
    (net (code "76") (name "unconnected-(MCU-SCK-Pad18)") (class "Default")
      (node (ref "MCU") (pin "18") (pinfunction "SCK_18") (pintype "passive"))
    )
    (net (code "77") (name "unconnected-(MCU-TX1-Pad14)") (class "Default")
      (node (ref "MCU") (pin "14") (pinfunction "TX1_14") (pintype "passive"))
    )
    (net (code "78") (name "unconnected-(MCU-USB-Pad3)") (class "Default")
      (node (ref "MCU") (pin "3") (pinfunction "USB_3") (pintype "passive"))
    )
  )
)
